# schematic.net
KiCad netlist of a schematic drawn in EAGLE
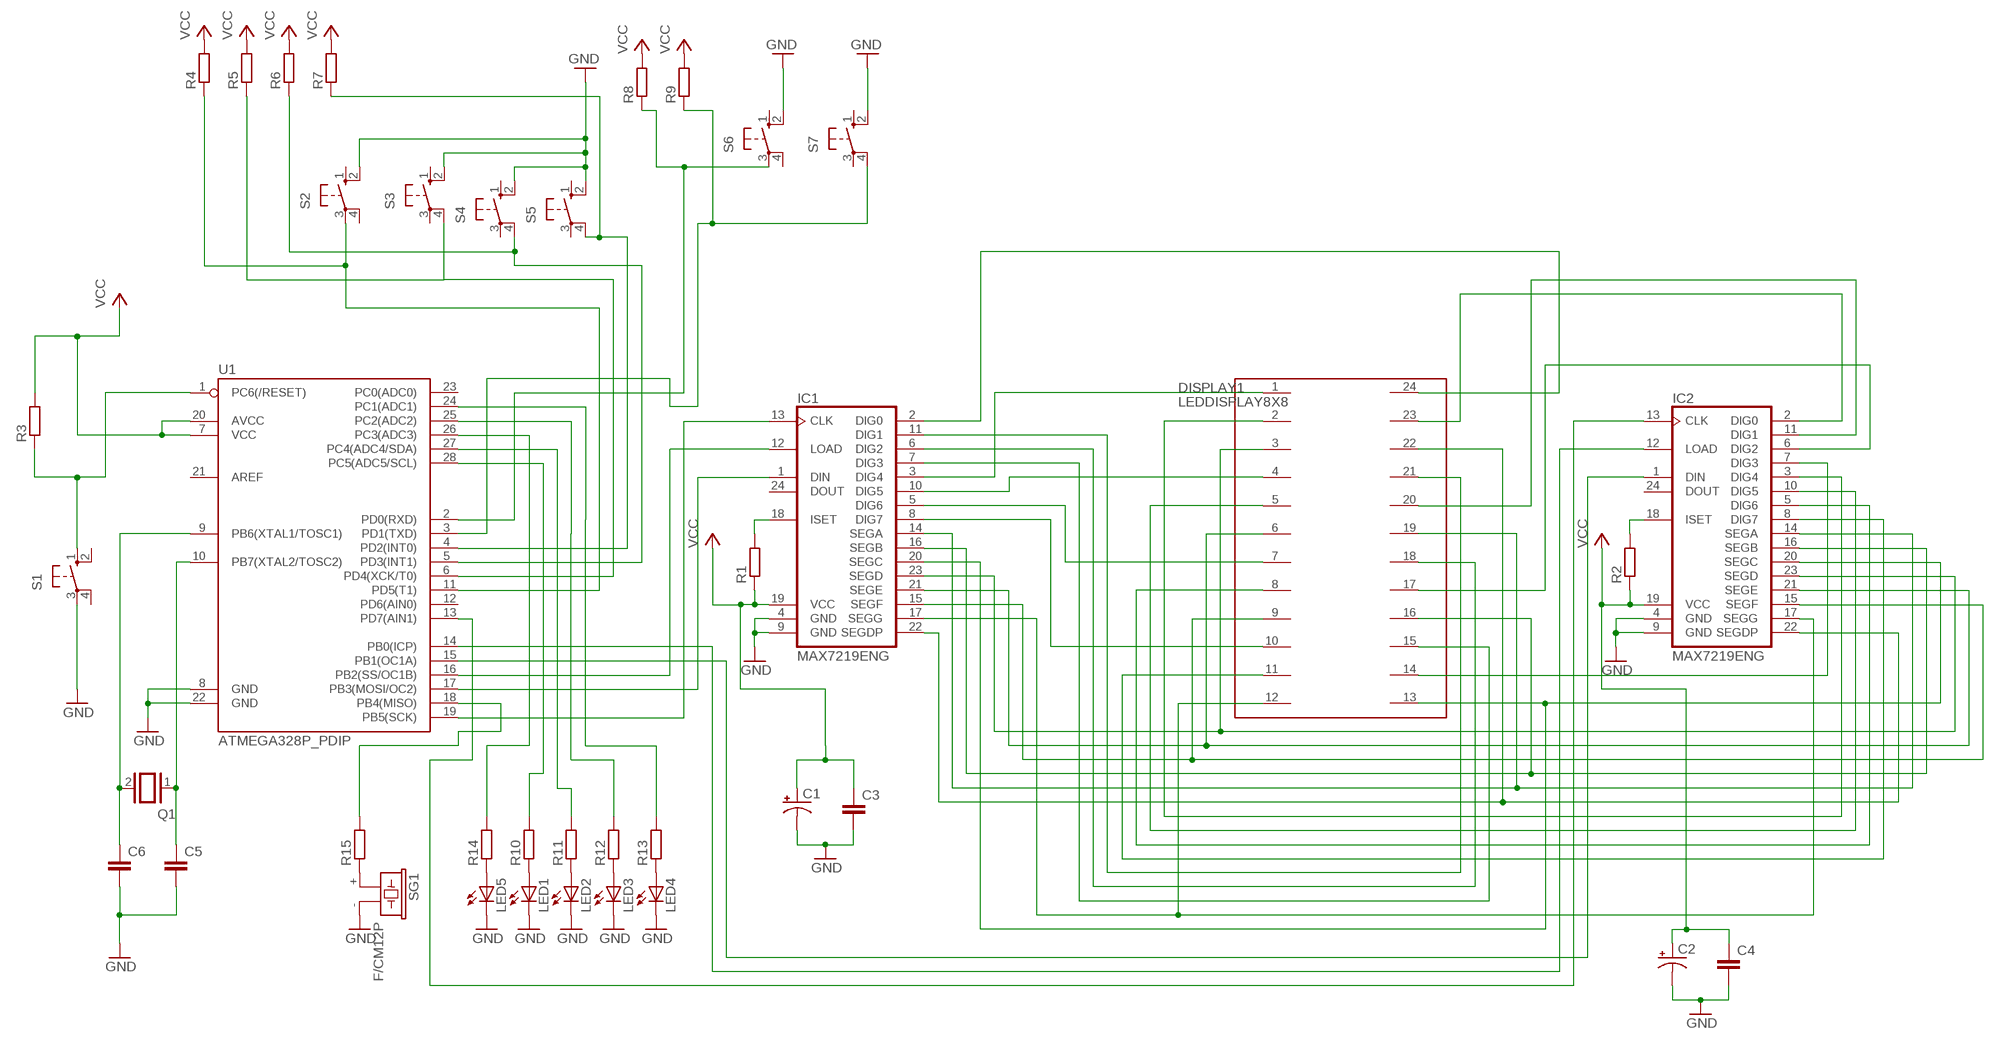
[diagram p0: schematic, sheet 1]

(export (version "E")
  (design (tool "Eeschema 10.0.6"))
  (components
    (comp (ref "C1")
      (value "CPOL-USE2.5-6")
      (footprint "eagle-import:E2,5-6")
      (libsource (lib "eagle-import") (part "CPOL-USE2.5-6"))
    )
    (comp (ref "C2")
      (value "CPOL-USE2.5-6")
      (footprint "eagle-import:E2,5-6")
      (libsource (lib "eagle-import") (part "CPOL-USE2.5-6"))
    )
    (comp (ref "C3")
      (value "C-EU025-024X044")
      (footprint "eagle-import:C025-024X044")
      (libsource (lib "eagle-import") (part "C-EU025-024X044"))
    )
    (comp (ref "C4")
      (value "C-EU025-024X044")
      (footprint "eagle-import:C025-024X044")
      (libsource (lib "eagle-import") (part "C-EU025-024X044"))
    )
    (comp (ref "C5")
      (value "C-EU025-024X044")
      (footprint "eagle-import:C025-024X044")
      (libsource (lib "eagle-import") (part "C-EU025-024X044"))
    )
    (comp (ref "C6")
      (value "C-EU025-024X044")
      (footprint "eagle-import:C025-024X044")
      (libsource (lib "eagle-import") (part "C-EU025-024X044"))
    )
    (comp (ref "DISPLAY1")
      (value "LEDDISPLAY8X8")
      (footprint "eagle-import:LEDDISPLAY8X8")
      (libsource (lib "eagle-import") (part "LEDDISPLAY8X8"))
    )
    (comp (ref "IC1")
      (value "MAX7219ENG")
      (footprint "eagle-import:DIL24-3")
      (libsource (lib "eagle-import") (part "MAX7219NGE"))
    )
    (comp (ref "IC2")
      (value "MAX7219ENG")
      (footprint "eagle-import:DIL24-3")
      (libsource (lib "eagle-import") (part "MAX7219NGE"))
    )
    (comp (ref "LED1")
      (value "LED5MM")
      (footprint "eagle-import:LED5MM")
      (libsource (lib "eagle-import") (part "LED5MM"))
    )
    (comp (ref "LED2")
      (value "LED5MM")
      (footprint "eagle-import:LED5MM")
      (libsource (lib "eagle-import") (part "LED5MM"))
    )
    (comp (ref "LED3")
      (value "LED5MM")
      (footprint "eagle-import:LED5MM")
      (libsource (lib "eagle-import") (part "LED5MM"))
    )
    (comp (ref "LED4")
      (value "LED5MM")
      (footprint "eagle-import:LED5MM")
      (libsource (lib "eagle-import") (part "LED5MM"))
    )
    (comp (ref "LED5")
      (value "LED5MM")
      (footprint "eagle-import:LED5MM")
      (libsource (lib "eagle-import") (part "LED5MM"))
    )
    (comp (ref "Q1")
      (value "XTAL")
      (footprint "eagle-import:Q")
      (libsource (lib "eagle-import") (part "XTAL"))
    )
    (comp (ref "R1")
      (value "R-EU_0204/7")
      (footprint "eagle-import:0204_7")
      (libsource (lib "eagle-import") (part "R-EU_0204/7"))
    )
    (comp (ref "R2")
      (value "R-EU_0204/7")
      (footprint "eagle-import:0204_7")
      (libsource (lib "eagle-import") (part "R-EU_0204/7"))
    )
    (comp (ref "R3")
      (value "R-EU_0204/7")
      (footprint "eagle-import:0204_7")
      (libsource (lib "eagle-import") (part "R-EU_0204/7"))
    )
    (comp (ref "R4")
      (value "R-EU_0204/7")
      (footprint "eagle-import:0204_7")
      (libsource (lib "eagle-import") (part "R-EU_0204/7"))
    )
    (comp (ref "R5")
      (value "R-EU_0204/7")
      (footprint "eagle-import:0204_7")
      (libsource (lib "eagle-import") (part "R-EU_0204/7"))
    )
    (comp (ref "R6")
      (value "R-EU_0204/7")
      (footprint "eagle-import:0204_7")
      (libsource (lib "eagle-import") (part "R-EU_0204/7"))
    )
    (comp (ref "R7")
      (value "R-EU_0204/7")
      (footprint "eagle-import:0204_7")
      (libsource (lib "eagle-import") (part "R-EU_0204/7"))
    )
    (comp (ref "R8")
      (value "R-EU_0204/7")
      (footprint "eagle-import:0204_7")
      (libsource (lib "eagle-import") (part "R-EU_0204/7"))
    )
    (comp (ref "R9")
      (value "R-EU_0204/7")
      (footprint "eagle-import:0204_7")
      (libsource (lib "eagle-import") (part "R-EU_0204/7"))
    )
    (comp (ref "R10")
      (value "R-EU_0204/7")
      (footprint "eagle-import:0204_7")
      (libsource (lib "eagle-import") (part "R-EU_0204/7"))
    )
    (comp (ref "R11")
      (value "R-EU_0204/7")
      (footprint "eagle-import:0204_7")
      (libsource (lib "eagle-import") (part "R-EU_0204/7"))
    )
    (comp (ref "R12")
      (value "R-EU_0204/7")
      (footprint "eagle-import:0204_7")
      (libsource (lib "eagle-import") (part "R-EU_0204/7"))
    )
    (comp (ref "R13")
      (value "R-EU_0204/7")
      (footprint "eagle-import:0204_7")
      (libsource (lib "eagle-import") (part "R-EU_0204/7"))
    )
    (comp (ref "R14")
      (value "R-EU_0204/7")
      (footprint "eagle-import:0204_7")
      (libsource (lib "eagle-import") (part "R-EU_0204/7"))
    )
    (comp (ref "R15")
      (value "R-EU_0204/7")
      (footprint "eagle-import:0204_7")
      (libsource (lib "eagle-import") (part "R-EU_0204/7"))
    )
    (comp (ref "S1")
      (value "10-XX")
      (footprint "eagle-import:B3F-10XX")
      (fields (field (name "MPN") "B3F-1000"))
      (libsource (lib "eagle-import") (part "10-XX"))
    )
    (comp (ref "S2")
      (value "40-XX")
      (footprint "eagle-import:B3F-40XX")
      (fields (field (name "MF") "OMRON COMPONENTS USA") (field (name "MPN") "B3F-4000"))
      (libsource (lib "eagle-import") (part "40-XX"))
    )
    (comp (ref "S3")
      (value "40-XX")
      (footprint "eagle-import:B3F-40XX")
      (fields (field (name "MF") "OMRON COMPONENTS USA") (field (name "MPN") "B3F-4000"))
      (libsource (lib "eagle-import") (part "40-XX"))
    )
    (comp (ref "S4")
      (value "40-XX")
      (footprint "eagle-import:B3F-40XX")
      (fields (field (name "MF") "OMRON COMPONENTS USA") (field (name "MPN") "B3F-4000"))
      (libsource (lib "eagle-import") (part "40-XX"))
    )
    (comp (ref "S5")
      (value "40-XX")
      (footprint "eagle-import:B3F-40XX")
      (fields (field (name "MF") "OMRON COMPONENTS USA") (field (name "MPN") "B3F-4000"))
      (libsource (lib "eagle-import") (part "40-XX"))
    )
    (comp (ref "S6")
      (value "40-XX")
      (footprint "eagle-import:B3F-40XX")
      (fields (field (name "MF") "OMRON COMPONENTS USA") (field (name "MPN") "B3F-4000"))
      (libsource (lib "eagle-import") (part "40-XX"))
    )
    (comp (ref "S7")
      (value "40-XX")
      (footprint "eagle-import:B3F-40XX")
      (fields (field (name "MF") "OMRON COMPONENTS USA") (field (name "MPN") "B3F-4000"))
      (libsource (lib "eagle-import") (part "40-XX"))
    )
    (comp (ref "SG1")
      (value "F/CM12P")
      (footprint "eagle-import:F_CM12P")
      (libsource (lib "eagle-import") (part "F/CM12P"))
    )
    (comp (ref "U1")
      (value "ATMEGA328P_PDIP")
      (footprint "eagle-import:DIL28-3")
      (libsource (lib "eagle-import") (part "ATMEGA328P_PDIP"))
    )
  )
  (nets
    (net (code "1") (name "GND") (class "Default")
      (node (ref "C1") (pin "-") (pinfunction "-_-") (pintype "passive"))
      (node (ref "C2") (pin "-") (pinfunction "-_-") (pintype "passive"))
      (node (ref "C3") (pin "2") (pinfunction "2_2") (pintype "passive"))
      (node (ref "C4") (pin "2") (pinfunction "2_2") (pintype "passive"))
      (node (ref "C5") (pin "2") (pinfunction "2_2") (pintype "passive"))
      (node (ref "C6") (pin "2") (pinfunction "2_2") (pintype "passive"))
      (node (ref "IC1") (pin "4") (pinfunction "GND_4") (pintype "power_in"))
      (node (ref "IC1") (pin "9") (pinfunction "GND_9") (pintype "power_in"))
      (node (ref "IC2") (pin "4") (pinfunction "GND_4") (pintype "power_in"))
      (node (ref "IC2") (pin "9") (pinfunction "GND_9") (pintype "power_in"))
      (node (ref "LED1") (pin "K") (pinfunction "C_K") (pintype "passive"))
      (node (ref "LED2") (pin "K") (pinfunction "C_K") (pintype "passive"))
      (node (ref "LED3") (pin "K") (pinfunction "C_K") (pintype "passive"))
      (node (ref "LED4") (pin "K") (pinfunction "C_K") (pintype "passive"))
      (node (ref "LED5") (pin "K") (pinfunction "C_K") (pintype "passive"))
      (node (ref "S1") (pin "3") (pinfunction "P_3") (pintype "passive"))
      (node (ref "S2") (pin "2") (pinfunction "S1_2") (pintype "passive"))
      (node (ref "S3") (pin "2") (pinfunction "S1_2") (pintype "passive"))
      (node (ref "S4") (pin "2") (pinfunction "S1_2") (pintype "passive"))
      (node (ref "S5") (pin "2") (pinfunction "S1_2") (pintype "passive"))
      (node (ref "S6") (pin "2") (pinfunction "S1_2") (pintype "passive"))
      (node (ref "S7") (pin "2") (pinfunction "S1_2") (pintype "passive"))
      (node (ref "SG1") (pin "-") (pinfunction "2_-") (pintype "passive"))
      (node (ref "U1") (pin "22") (pinfunction "GND_22") (pintype "bidirectional"))
      (node (ref "U1") (pin "8") (pinfunction "GND_8") (pintype "bidirectional"))
    )
    (net (code "2") (name "Net-(DISPLAY1-P$1)") (class "Default")
      (node (ref "DISPLAY1") (pin "1") (pinfunction "P$1_1") (pintype "bidirectional"))
      (node (ref "IC1") (pin "3") (pinfunction "DIG4_3") (pintype "output"))
    )
    (net (code "3") (name "Net-(DISPLAY1-P$2)") (class "Default")
      (node (ref "DISPLAY1") (pin "2") (pinfunction "P$2_2") (pintype "bidirectional"))
      (node (ref "IC2") (pin "3") (pinfunction "DIG4_3") (pintype "output"))
    )
    (net (code "4") (name "Net-(DISPLAY1-P$3)") (class "Default")
      (node (ref "DISPLAY1") (pin "3") (pinfunction "P$3_3") (pintype "bidirectional"))
      (node (ref "IC1") (pin "23") (pinfunction "SEGD_23") (pintype "output"))
      (node (ref "IC2") (pin "23") (pinfunction "SEGD_23") (pintype "output"))
    )
    (net (code "5") (name "Net-(DISPLAY1-P$4)") (class "Default")
      (node (ref "DISPLAY1") (pin "4") (pinfunction "P$4_4") (pintype "bidirectional"))
      (node (ref "IC1") (pin "10") (pinfunction "DIG5_10") (pintype "output"))
    )
    (net (code "6") (name "Net-(DISPLAY1-P$5)") (class "Default")
      (node (ref "DISPLAY1") (pin "5") (pinfunction "P$5_5") (pintype "bidirectional"))
      (node (ref "IC2") (pin "10") (pinfunction "DIG5_10") (pintype "output"))
    )
    (net (code "7") (name "Net-(DISPLAY1-P$6)") (class "Default")
      (node (ref "DISPLAY1") (pin "6") (pinfunction "P$6_6") (pintype "bidirectional"))
      (node (ref "IC1") (pin "21") (pinfunction "SEGE_21") (pintype "output"))
      (node (ref "IC2") (pin "21") (pinfunction "SEGE_21") (pintype "output"))
    )
    (net (code "8") (name "Net-(DISPLAY1-P$7)") (class "Default")
      (node (ref "DISPLAY1") (pin "7") (pinfunction "P$7_7") (pintype "bidirectional"))
      (node (ref "IC1") (pin "5") (pinfunction "DIG6_5") (pintype "output"))
    )
    (net (code "9") (name "Net-(DISPLAY1-P$8)") (class "Default")
      (node (ref "DISPLAY1") (pin "8") (pinfunction "P$8_8") (pintype "bidirectional"))
      (node (ref "IC2") (pin "5") (pinfunction "DIG6_5") (pintype "output"))
    )
    (net (code "10") (name "Net-(DISPLAY1-P$9)") (class "Default")
      (node (ref "DISPLAY1") (pin "9") (pinfunction "P$9_9") (pintype "bidirectional"))
      (node (ref "IC1") (pin "15") (pinfunction "SEGF_15") (pintype "output"))
      (node (ref "IC2") (pin "15") (pinfunction "SEGF_15") (pintype "output"))
    )
    (net (code "11") (name "Net-(DISPLAY1-P$10)") (class "Default")
      (node (ref "DISPLAY1") (pin "10") (pinfunction "P$10_10") (pintype "bidirectional"))
      (node (ref "IC1") (pin "8") (pinfunction "DIG7_8") (pintype "output"))
    )
    (net (code "12") (name "Net-(DISPLAY1-P$11)") (class "Default")
      (node (ref "DISPLAY1") (pin "11") (pinfunction "P$11_11") (pintype "bidirectional"))
      (node (ref "IC2") (pin "8") (pinfunction "DIG7_8") (pintype "output"))
    )
    (net (code "13") (name "Net-(DISPLAY1-P$12)") (class "Default")
      (node (ref "DISPLAY1") (pin "12") (pinfunction "P$12_12") (pintype "bidirectional"))
      (node (ref "IC1") (pin "17") (pinfunction "SEGG_17") (pintype "output"))
      (node (ref "IC2") (pin "17") (pinfunction "SEGG_17") (pintype "output"))
    )
    (net (code "14") (name "Net-(DISPLAY1-P$13)") (class "Default")
      (node (ref "DISPLAY1") (pin "13") (pinfunction "P$13_13") (pintype "bidirectional"))
      (node (ref "IC1") (pin "20") (pinfunction "SEGC_20") (pintype "output"))
      (node (ref "IC2") (pin "20") (pinfunction "SEGC_20") (pintype "output"))
    )
    (net (code "15") (name "Net-(DISPLAY1-P$14)") (class "Default")
      (node (ref "DISPLAY1") (pin "14") (pinfunction "P$14_14") (pintype "bidirectional"))
      (node (ref "IC2") (pin "7") (pinfunction "DIG3_7") (pintype "output"))
    )
    (net (code "16") (name "Net-(DISPLAY1-P$15)") (class "Default")
      (node (ref "DISPLAY1") (pin "15") (pinfunction "P$15_15") (pintype "bidirectional"))
      (node (ref "IC1") (pin "7") (pinfunction "DIG3_7") (pintype "output"))
    )
    (net (code "17") (name "Net-(DISPLAY1-P$16)") (class "Default")
      (node (ref "DISPLAY1") (pin "16") (pinfunction "P$16_16") (pintype "bidirectional"))
      (node (ref "IC1") (pin "16") (pinfunction "SEGB_16") (pintype "output"))
      (node (ref "IC2") (pin "16") (pinfunction "SEGB_16") (pintype "output"))
    )
    (net (code "18") (name "Net-(DISPLAY1-P$17)") (class "Default")
      (node (ref "DISPLAY1") (pin "17") (pinfunction "P$17_17") (pintype "bidirectional"))
      (node (ref "IC2") (pin "6") (pinfunction "DIG2_6") (pintype "output"))
    )
    (net (code "19") (name "Net-(DISPLAY1-P$18)") (class "Default")
      (node (ref "DISPLAY1") (pin "18") (pinfunction "P$18_18") (pintype "bidirectional"))
      (node (ref "IC1") (pin "6") (pinfunction "DIG2_6") (pintype "output"))
    )
    (net (code "20") (name "Net-(DISPLAY1-P$19)") (class "Default")
      (node (ref "DISPLAY1") (pin "19") (pinfunction "P$19_19") (pintype "bidirectional"))
      (node (ref "IC1") (pin "14") (pinfunction "SEGA_14") (pintype "output"))
      (node (ref "IC2") (pin "14") (pinfunction "SEGA_14") (pintype "output"))
    )
    (net (code "21") (name "Net-(DISPLAY1-P$20)") (class "Default")
      (node (ref "DISPLAY1") (pin "20") (pinfunction "P$20_20") (pintype "bidirectional"))
      (node (ref "IC2") (pin "11") (pinfunction "DIG1_11") (pintype "output"))
    )
    (net (code "22") (name "Net-(DISPLAY1-P$21)") (class "Default")
      (node (ref "DISPLAY1") (pin "21") (pinfunction "P$21_21") (pintype "bidirectional"))
      (node (ref "IC1") (pin "11") (pinfunction "DIG1_11") (pintype "output"))
    )
    (net (code "23") (name "Net-(DISPLAY1-P$22)") (class "Default")
      (node (ref "DISPLAY1") (pin "22") (pinfunction "P$22_22") (pintype "bidirectional"))
      (node (ref "IC1") (pin "22") (pinfunction "SEGDP_22") (pintype "output"))
      (node (ref "IC2") (pin "22") (pinfunction "SEGDP_22") (pintype "output"))
    )
    (net (code "24") (name "Net-(DISPLAY1-P$23)") (class "Default")
      (node (ref "DISPLAY1") (pin "23") (pinfunction "P$23_23") (pintype "bidirectional"))
      (node (ref "IC2") (pin "2") (pinfunction "DIG0_2") (pintype "output"))
    )
    (net (code "25") (name "Net-(DISPLAY1-P$24)") (class "Default")
      (node (ref "DISPLAY1") (pin "24") (pinfunction "P$24_24") (pintype "bidirectional"))
      (node (ref "IC1") (pin "2") (pinfunction "DIG0_2") (pintype "output"))
    )
    (net (code "26") (name "Net-(IC1-CLK)") (class "Default")
      (node (ref "IC1") (pin "13") (pinfunction "CLK_13") (pintype "input"))
      (node (ref "U1") (pin "19") (pinfunction "PB5(SCK)_19") (pintype "bidirectional"))
    )
    (net (code "27") (name "Net-(IC1-DIN)") (class "Default")
      (node (ref "IC1") (pin "1") (pinfunction "DIN_1") (pintype "input"))
      (node (ref "U1") (pin "17") (pinfunction "PB3(MOSI/OC2)_17") (pintype "bidirectional"))
    )
    (net (code "28") (name "Net-(IC1-ISET)") (class "Default")
      (node (ref "IC1") (pin "18") (pinfunction "ISET_18") (pintype "input"))
      (node (ref "R1") (pin "2") (pinfunction "2_2") (pintype "passive"))
    )
    (net (code "29") (name "Net-(IC1-LOAD)") (class "Default")
      (node (ref "IC1") (pin "12") (pinfunction "LOAD_12") (pintype "input"))
      (node (ref "U1") (pin "16") (pinfunction "PB2(SS/OC1B)_16") (pintype "bidirectional"))
    )
    (net (code "30") (name "Net-(IC2-CLK)") (class "Default")
      (node (ref "IC2") (pin "13") (pinfunction "CLK_13") (pintype "input"))
      (node (ref "U1") (pin "13") (pinfunction "PD7(AIN1)_13") (pintype "bidirectional"))
    )
    (net (code "31") (name "Net-(IC2-DIN)") (class "Default")
      (node (ref "IC2") (pin "1") (pinfunction "DIN_1") (pintype "input"))
      (node (ref "U1") (pin "15") (pinfunction "PB1(OC1A)_15") (pintype "bidirectional"))
    )
    (net (code "32") (name "Net-(IC2-ISET)") (class "Default")
      (node (ref "IC2") (pin "18") (pinfunction "ISET_18") (pintype "input"))
      (node (ref "R2") (pin "2") (pinfunction "2_2") (pintype "passive"))
    )
    (net (code "33") (name "Net-(IC2-LOAD)") (class "Default")
      (node (ref "IC2") (pin "12") (pinfunction "LOAD_12") (pintype "input"))
      (node (ref "U1") (pin "14") (pinfunction "PB0(ICP)_14") (pintype "bidirectional"))
    )
    (net (code "34") (name "Net-(LED1-PadA)") (class "Default")
      (node (ref "LED1") (pin "A") (pinfunction "A_A") (pintype "passive"))
      (node (ref "R10") (pin "1") (pinfunction "1_1") (pintype "passive"))
    )
    (net (code "35") (name "Net-(LED2-PadA)") (class "Default")
      (node (ref "LED2") (pin "A") (pinfunction "A_A") (pintype "passive"))
      (node (ref "R11") (pin "1") (pinfunction "1_1") (pintype "passive"))
    )
    (net (code "36") (name "Net-(LED3-PadA)") (class "Default")
      (node (ref "LED3") (pin "A") (pinfunction "A_A") (pintype "passive"))
      (node (ref "R12") (pin "1") (pinfunction "1_1") (pintype "passive"))
    )
    (net (code "37") (name "Net-(LED4-PadA)") (class "Default")
      (node (ref "LED4") (pin "A") (pinfunction "A_A") (pintype "passive"))
      (node (ref "R13") (pin "1") (pinfunction "1_1") (pintype "passive"))
    )
    (net (code "38") (name "Net-(LED5-PadA)") (class "Default")
      (node (ref "LED5") (pin "A") (pinfunction "A_A") (pintype "passive"))
      (node (ref "R14") (pin "1") (pinfunction "1_1") (pintype "passive"))
    )
    (net (code "39") (name "Net-(S1-S)") (class "Default")
      (node (ref "R3") (pin "1") (pinfunction "1_1") (pintype "passive"))
      (node (ref "S1") (pin "1") (pinfunction "S_1") (pintype "passive"))
      (node (ref "U1") (pin "1") (pinfunction "PC6(/RESET)_1") (pintype "bidirectional"))
    )
    (net (code "40") (name "Net-(S2-P)") (class "Default")
      (node (ref "R4") (pin "1") (pinfunction "1_1") (pintype "passive"))
      (node (ref "S2") (pin "3") (pinfunction "P_3") (pintype "passive"))
      (node (ref "U1") (pin "11") (pinfunction "PD5(T1)_11") (pintype "bidirectional"))
    )
    (net (code "41") (name "Net-(S3-P1)") (class "Default")
      (node (ref "R5") (pin "1") (pinfunction "1_1") (pintype "passive"))
      (node (ref "S3") (pin "4") (pinfunction "P1_4") (pintype "passive"))
      (node (ref "U1") (pin "6") (pinfunction "PD4(XCK/T0)_6") (pintype "bidirectional"))
    )
    (net (code "42") (name "Net-(S4-P1)") (class "Default")
      (node (ref "R6") (pin "1") (pinfunction "1_1") (pintype "passive"))
      (node (ref "S4") (pin "4") (pinfunction "P1_4") (pintype "passive"))
      (node (ref "U1") (pin "5") (pinfunction "PD3(INT1)_5") (pintype "bidirectional"))
    )
    (net (code "43") (name "Net-(S5-P1)") (class "Default")
      (node (ref "R7") (pin "1") (pinfunction "1_1") (pintype "passive"))
      (node (ref "S5") (pin "4") (pinfunction "P1_4") (pintype "passive"))
      (node (ref "U1") (pin "4") (pinfunction "PD2(INT0)_4") (pintype "bidirectional"))
    )
    (net (code "44") (name "Net-(S6-P)") (class "Default")
      (node (ref "R8") (pin "1") (pinfunction "1_1") (pintype "passive"))
      (node (ref "S6") (pin "3") (pinfunction "P_3") (pintype "passive"))
      (node (ref "U1") (pin "2") (pinfunction "PD0(RXD)_2") (pintype "bidirectional"))
    )
    (net (code "45") (name "Net-(S7-P1)") (class "Default")
      (node (ref "R9") (pin "1") (pinfunction "1_1") (pintype "passive"))
      (node (ref "S7") (pin "4") (pinfunction "P1_4") (pintype "passive"))
      (node (ref "U1") (pin "3") (pinfunction "PD1(TXD)_3") (pintype "bidirectional"))
    )
    (net (code "46") (name "Net-(SG1-1)") (class "Default")
      (node (ref "R15") (pin "1") (pinfunction "1_1") (pintype "passive"))
      (node (ref "SG1") (pin "+") (pinfunction "1_+") (pintype "passive"))
    )
    (net (code "47") (name "Net-(U1-PB4(MISO))") (class "Default")
      (node (ref "R15") (pin "2") (pinfunction "2_2") (pintype "passive"))
      (node (ref "U1") (pin "18") (pinfunction "PB4(MISO)_18") (pintype "bidirectional"))
    )
    (net (code "48") (name "Net-(U1-PB6(XTAL1{slash}TOSC1))") (class "Default")
      (node (ref "C6") (pin "1") (pinfunction "1_1") (pintype "passive"))
      (node (ref "Q1") (pin "2") (pinfunction "2_2") (pintype "passive"))
      (node (ref "U1") (pin "9") (pinfunction "PB6(XTAL1/TOSC1)_9") (pintype "bidirectional"))
    )
    (net (code "49") (name "Net-(U1-PB7(XTAL2{slash}TOSC2))") (class "Default")
      (node (ref "C5") (pin "1") (pinfunction "1_1") (pintype "passive"))
      (node (ref "Q1") (pin "1") (pinfunction "1_1") (pintype "passive"))
      (node (ref "U1") (pin "10") (pinfunction "PB7(XTAL2/TOSC2)_10") (pintype "bidirectional"))
    )
    (net (code "50") (name "Net-(U1-PC1(ADC1))") (class "Default")
      (node (ref "R13") (pin "2") (pinfunction "2_2") (pintype "passive"))
      (node (ref "U1") (pin "24") (pinfunction "PC1(ADC1)_24") (pintype "bidirectional"))
    )
    (net (code "51") (name "Net-(U1-PC2(ADC2))") (class "Default")
      (node (ref "R12") (pin "2") (pinfunction "2_2") (pintype "passive"))
      (node (ref "U1") (pin "25") (pinfunction "PC2(ADC2)_25") (pintype "bidirectional"))
    )
    (net (code "52") (name "Net-(U1-PC3(ADC3))") (class "Default")
      (node (ref "R14") (pin "2") (pinfunction "2_2") (pintype "passive"))
      (node (ref "U1") (pin "26") (pinfunction "PC3(ADC3)_26") (pintype "bidirectional"))
    )
    (net (code "53") (name "Net-(U1-PC4(ADC4{slash}SDA))") (class "Default")
      (node (ref "R11") (pin "2") (pinfunction "2_2") (pintype "passive"))
      (node (ref "U1") (pin "27") (pinfunction "PC4(ADC4/SDA)_27") (pintype "bidirectional"))
    )
    (net (code "54") (name "Net-(U1-PC5(ADC5{slash}SCL))") (class "Default")
      (node (ref "R10") (pin "2") (pinfunction "2_2") (pintype "passive"))
      (node (ref "U1") (pin "28") (pinfunction "PC5(ADC5/SCL)_28") (pintype "bidirectional"))
    )
    (net (code "55") (name "VCC") (class "Default")
      (node (ref "C1") (pin "+") (pinfunction "+_+") (pintype "passive"))
      (node (ref "C2") (pin "+") (pinfunction "+_+") (pintype "passive"))
      (node (ref "C3") (pin "1") (pinfunction "1_1") (pintype "passive"))
      (node (ref "C4") (pin "1") (pinfunction "1_1") (pintype "passive"))
      (node (ref "IC1") (pin "19") (pinfunction "VCC_19") (pintype "power_in"))
      (node (ref "IC2") (pin "19") (pinfunction "VCC_19") (pintype "power_in"))
      (node (ref "R1") (pin "1") (pinfunction "1_1") (pintype "passive"))
      (node (ref "R2") (pin "1") (pinfunction "1_1") (pintype "passive"))
      (node (ref "R3") (pin "2") (pinfunction "2_2") (pintype "passive"))
      (node (ref "R4") (pin "2") (pinfunction "2_2") (pintype "passive"))
      (node (ref "R5") (pin "2") (pinfunction "2_2") (pintype "passive"))
      (node (ref "R6") (pin "2") (pinfunction "2_2") (pintype "passive"))
      (node (ref "R7") (pin "2") (pinfunction "2_2") (pintype "passive"))
      (node (ref "R8") (pin "2") (pinfunction "2_2") (pintype "passive"))
      (node (ref "R9") (pin "2") (pinfunction "2_2") (pintype "passive"))
      (node (ref "U1") (pin "20") (pinfunction "AVCC_20") (pintype "bidirectional"))
      (node (ref "U1") (pin "7") (pinfunction "VCC_7") (pintype "bidirectional"))
    )
    (net (code "56") (name "unconnected-(IC1-DOUT-Pad24)") (class "Default")
      (node (ref "IC1") (pin "24") (pinfunction "DOUT_24") (pintype "output"))
    )
    (net (code "57") (name "unconnected-(IC2-DOUT-Pad24)") (class "Default")
      (node (ref "IC2") (pin "24") (pinfunction "DOUT_24") (pintype "output"))
    )
    (net (code "58") (name "unconnected-(S1-P1-Pad4)") (class "Default")
      (node (ref "S1") (pin "4") (pinfunction "P1_4") (pintype "passive"))
    )
    (net (code "59") (name "unconnected-(S1-S1-Pad2)") (class "Default")
      (node (ref "S1") (pin "2") (pinfunction "S1_2") (pintype "passive"))
    )
    (net (code "60") (name "unconnected-(S2-P1-Pad4)") (class "Default")
      (node (ref "S2") (pin "4") (pinfunction "P1_4") (pintype "passive"))
    )
    (net (code "61") (name "unconnected-(S2-S-Pad1)") (class "Default")
      (node (ref "S2") (pin "1") (pinfunction "S_1") (pintype "passive"))
    )
    (net (code "62") (name "unconnected-(S3-P-Pad3)") (class "Default")
      (node (ref "S3") (pin "3") (pinfunction "P_3") (pintype "passive"))
    )
    (net (code "63") (name "unconnected-(S3-S-Pad1)") (class "Default")
      (node (ref "S3") (pin "1") (pinfunction "S_1") (pintype "passive"))
    )
    (net (code "64") (name "unconnected-(S4-P-Pad3)") (class "Default")
      (node (ref "S4") (pin "3") (pinfunction "P_3") (pintype "passive"))
    )
    (net (code "65") (name "unconnected-(S4-S-Pad1)") (class "Default")
      (node (ref "S4") (pin "1") (pinfunction "S_1") (pintype "passive"))
    )
    (net (code "66") (name "unconnected-(S5-P-Pad3)") (class "Default")
      (node (ref "S5") (pin "3") (pinfunction "P_3") (pintype "passive"))
    )
    (net (code "67") (name "unconnected-(S5-S-Pad1)") (class "Default")
      (node (ref "S5") (pin "1") (pinfunction "S_1") (pintype "passive"))
    )
    (net (code "68") (name "unconnected-(S6-P1-Pad4)") (class "Default")
      (node (ref "S6") (pin "4") (pinfunction "P1_4") (pintype "passive"))
    )
    (net (code "69") (name "unconnected-(S6-S-Pad1)") (class "Default")
      (node (ref "S6") (pin "1") (pinfunction "S_1") (pintype "passive"))
    )
    (net (code "70") (name "unconnected-(S7-P-Pad3)") (class "Default")
      (node (ref "S7") (pin "3") (pinfunction "P_3") (pintype "passive"))
    )
    (net (code "71") (name "unconnected-(S7-S-Pad1)") (class "Default")
      (node (ref "S7") (pin "1") (pinfunction "S_1") (pintype "passive"))
    )
    (net (code "72") (name "unconnected-(U1-AREF-Pad21)") (class "Default")
      (node (ref "U1") (pin "21") (pinfunction "AREF_21") (pintype "bidirectional"))
    )
    (net (code "73") (name "unconnected-(U1-PC0(ADC0)-Pad23)") (class "Default")
      (node (ref "U1") (pin "23") (pinfunction "PC0(ADC0)_23") (pintype "bidirectional"))
    )
    (net (code "74") (name "unconnected-(U1-PD6(AIN0)-Pad12)") (class "Default")
      (node (ref "U1") (pin "12") (pinfunction "PD6(AIN0)_12") (pintype "bidirectional"))
    )
  )
)
